# STM32F407VE.net
KiCad netlist of a schematic drawn in Altium Designer
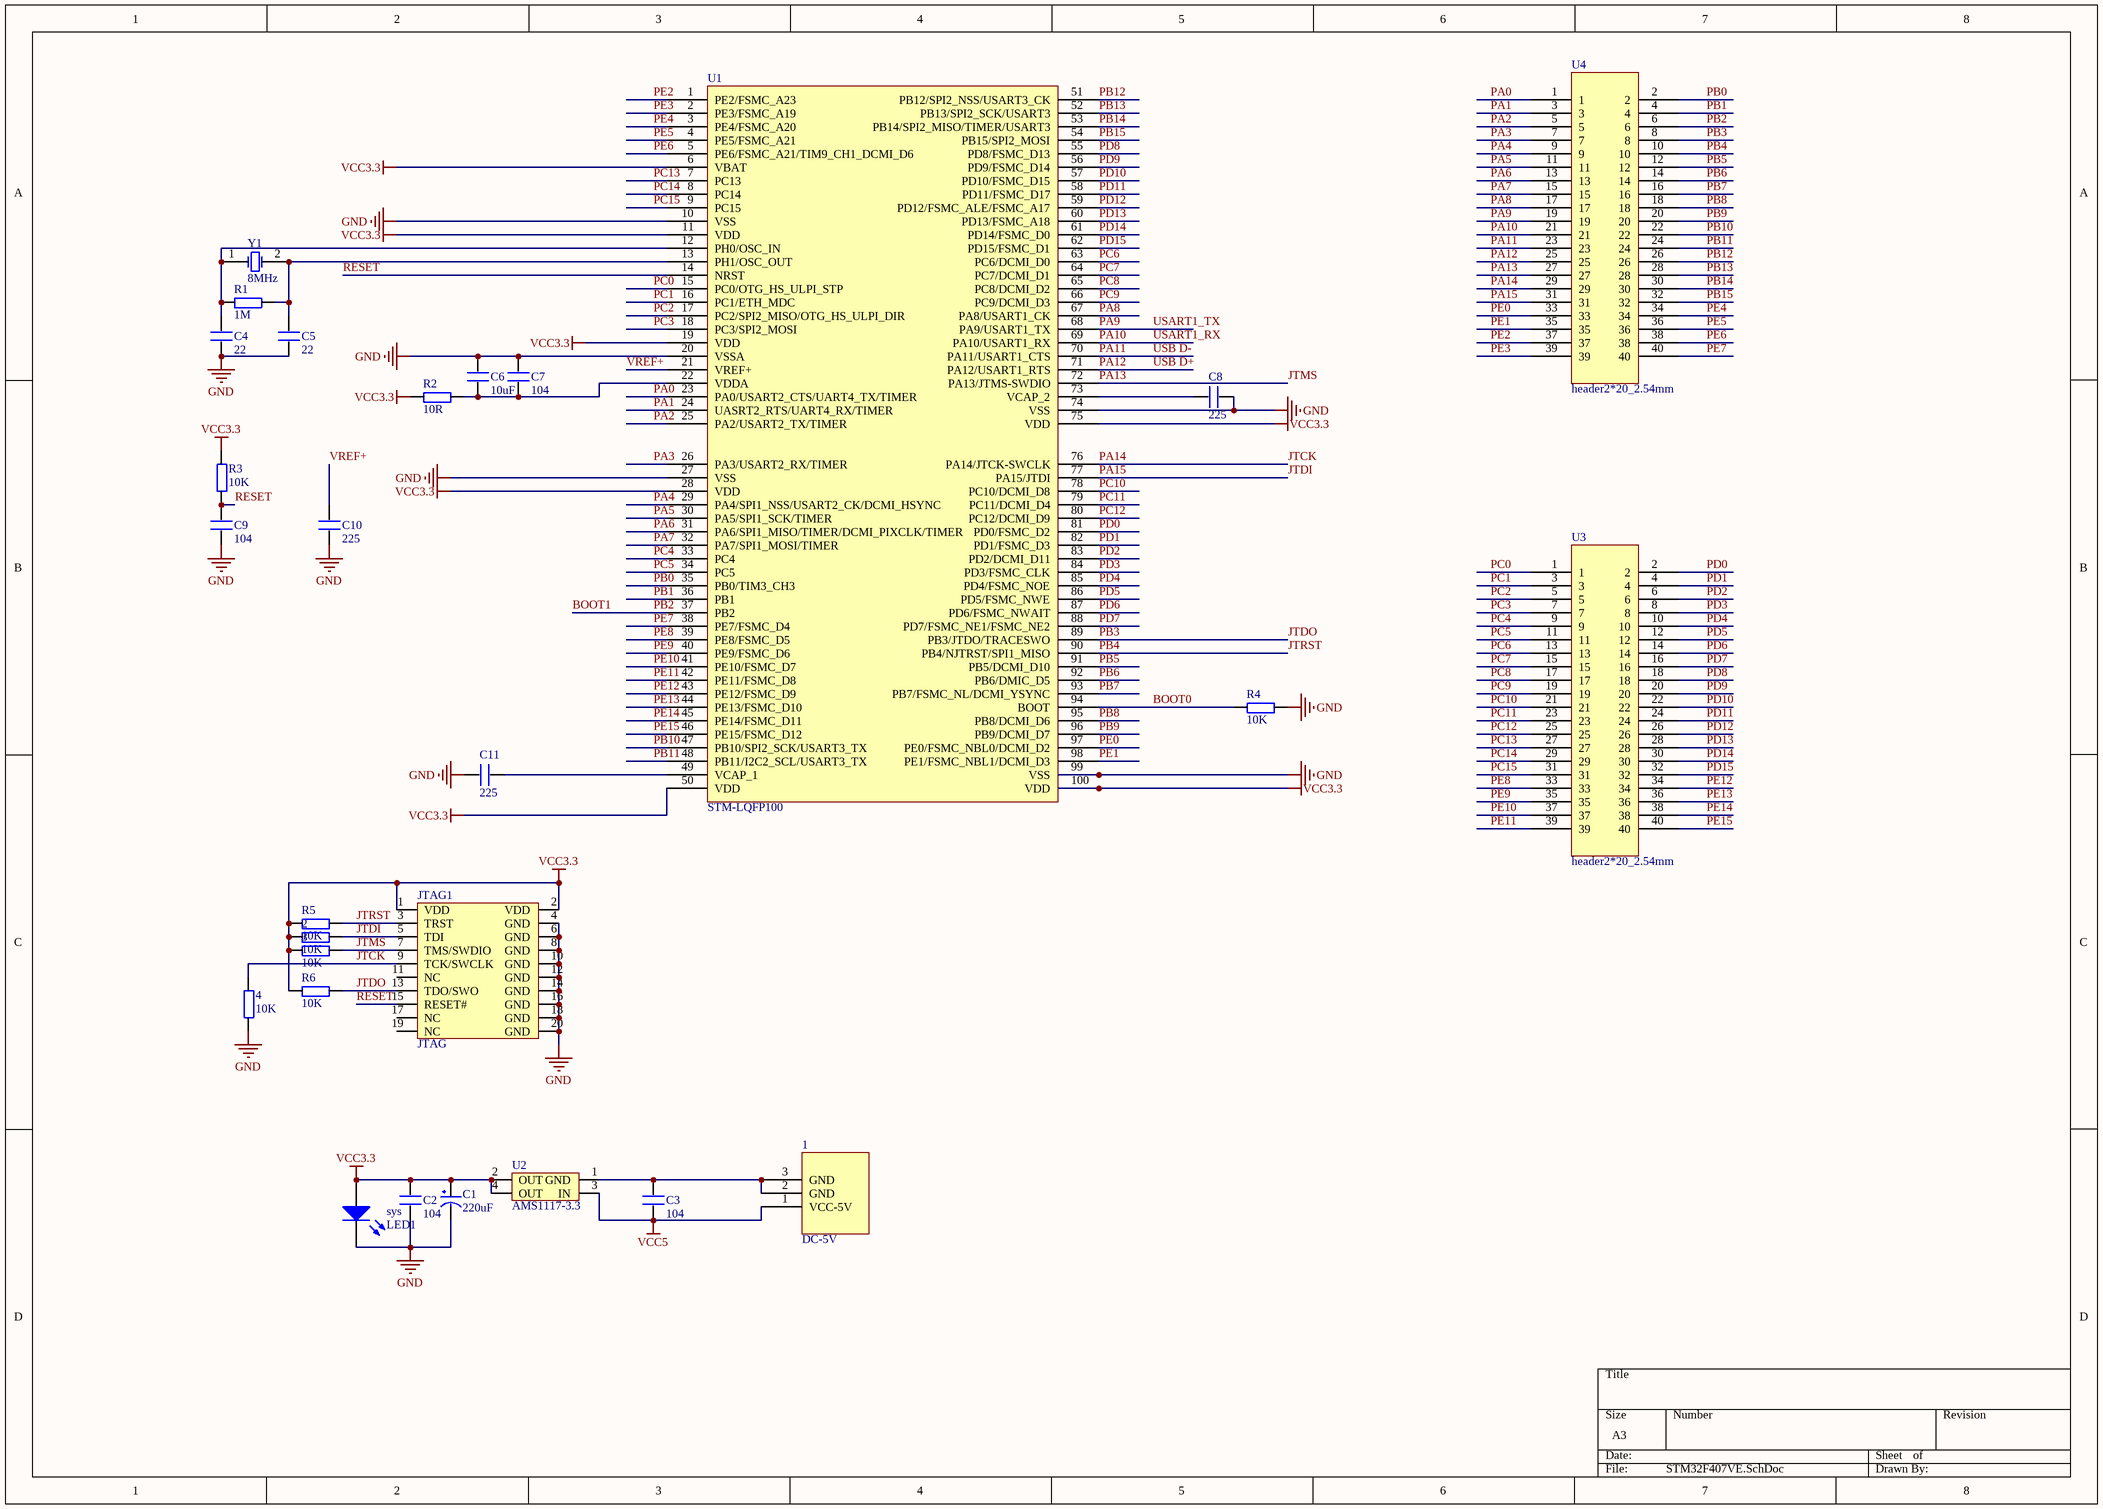
[diagram p0: STM32F407VE.SchDoc]

(export (version "E")
  (design (tool "Eeschema 10.0.6"))
  (components
    (comp (ref "1") (value "DC-5V") (footprint "DC-5V") (libsource (lib "Schlib1") (part "DC-5V")))
    (comp (ref "2") (value "10K") (footprint "0603P") (libsource (lib "Explorer STM32F407封装库") (part "R")))
    (comp (ref "3") (value "10K") (footprint "0603P") (libsource (lib "Explorer STM32F407封装库") (part "R")))
    (comp (ref "4") (value "10K") (footprint "0603P") (libsource (lib "Explorer STM32F407封装库") (part "R")))
    (comp (ref "C1")
      (value "220uF")
      (footprint "CC6.56.5")
      (libsource (lib "Explorer STM32F407封装库") (part "CAP"))
    )
    (comp (ref "C2") (value "104") (footprint "0603P") (libsource (lib "Explorer STM32F407封装库") (part "C")))
    (comp (ref "C3") (value "104") (footprint "0603P") (libsource (lib "Explorer STM32F407封装库") (part "C")))
    (comp (ref "C4") (value "22") (footprint "0603P") (libsource (lib "Explorer STM32F407封装库") (part "C")))
    (comp (ref "C5") (value "22") (footprint "0603P") (libsource (lib "Explorer STM32F407封装库") (part "C")))
    (comp (ref "C6") (value "10uF") (footprint "0603P") (libsource (lib "Explorer STM32F407封装库") (part "C")))
    (comp (ref "C7") (value "104") (footprint "0603P") (libsource (lib "Explorer STM32F407封装库") (part "C")))
    (comp (ref "C8") (value "225") (footprint "0603P") (libsource (lib "Explorer STM32F407封装库") (part "C")))
    (comp (ref "C9") (value "104") (footprint "0603P") (libsource (lib "Explorer STM32F407封装库") (part "C")))
    (comp (ref "C10") (value "225") (footprint "0603P") (libsource (lib "Explorer STM32F407封装库") (part "C")))
    (comp (ref "C11") (value "225") (footprint "0603P") (libsource (lib "Explorer STM32F407封装库") (part "C")))
    (comp (ref "JTAG1")
      (value "JTAG")
      (footprint "JTAG_20")
      (libsource (lib "Explorer STM32F407封装库") (part "JTAG"))
    )
    (comp (ref "R1") (value "1M") (footprint "0603P") (libsource (lib "Explorer STM32F407封装库") (part "R")))
    (comp (ref "R2") (value "10R") (footprint "0603P") (libsource (lib "Explorer STM32F407封装库") (part "R")))
    (comp (ref "R3") (value "10K") (footprint "0603P") (libsource (lib "Explorer STM32F407封装库") (part "R")))
    (comp (ref "R4") (value "10K") (footprint "0603P") (libsource (lib "Explorer STM32F407封装库") (part "R")))
    (comp (ref "R5") (value "10K") (footprint "0603P") (libsource (lib "Explorer STM32F407封装库") (part "R")))
    (comp (ref "R6") (value "10K") (footprint "0603P") (libsource (lib "Explorer STM32F407封装库") (part "R")))
    (comp (ref "sys")
      (value "LED1")
      (footprint "SMDLED")
      (description "Typical RED, GREEN, YELLOW, AMBER GaAs LED")
      (fields (field (name "PUBLISHER") "Altium Limited"))
      (libsource (lib "Explorer STM32F407封装库") (part "LED2"))
    )
    (comp (ref "U1")
      (value "STM-LQFP100")
      (footprint "STM-LQFP100_N")
      (libsource (lib "Schlib1") (part "STM-LQFP100"))
    )
    (comp (ref "U2")
      (value "AMS1117-3.3")
      (footprint "AMS1117")
      (libsource (lib "Explorer STM32F407封装库") (part "AMS1117"))
    )
    (comp (ref "U3")
      (value "header2*20_2.54mm")
      (footprint "header2*20_2.54mm")
      (libsource (lib "Schlib1") (part "header2*20_2.54mm"))
    )
    (comp (ref "U4")
      (value "header2*20_2.54mm")
      (footprint "header2*20_2.54mm")
      (libsource (lib "Schlib1") (part "header2*20_2.54mm"))
    )
    (comp (ref "Y1")
      (value "8MHz")
      (footprint "XTAL_US")
      (description "Crystal Oscillator")
      (fields (field (name "PUBLISHER") "Altium Limited"))
      (libsource (lib "Explorer STM32F407封装库") (part "XTAL"))
    )
  )
  (nets
    (net (code "1") (name "/BOOT0") (class "Default")
      (node (ref "R4") (pin "1") (pintype "passive"))
      (node (ref "U1") (pin "94") (pinfunction "BOOT_94") (pintype "passive"))
    )
    (net (code "2") (name "/BOOT1") (class "Default")
      (node (ref "U1") (pin "37") (pinfunction "PB2_37") (pintype "passive"))
      (node (ref "U4") (pin "6") (pinfunction "6_6") (pintype "passive"))
    )
    (net (code "3") (name "/JTCK") (class "Default")
      (node (ref "4") (pin "2") (pintype "passive"))
      (node (ref "JTAG1") (pin "9") (pinfunction "TCK/SWCLK_9") (pintype "passive"))
      (node (ref "U1") (pin "76") (pinfunction "PA14/JTCK-SWCLK_76") (pintype "passive"))
      (node (ref "U4") (pin "29") (pinfunction "29_29") (pintype "passive"))
    )
    (net (code "4") (name "/JTDI") (class "Default")
      (node (ref "2") (pin "2") (pintype "passive"))
      (node (ref "JTAG1") (pin "5") (pinfunction "TDI_5") (pintype "passive"))
      (node (ref "U1") (pin "77") (pinfunction "PA15/JTDI_77") (pintype "passive"))
      (node (ref "U4") (pin "31") (pinfunction "31_31") (pintype "passive"))
    )
    (net (code "5") (name "/JTDO") (class "Default")
      (node (ref "JTAG1") (pin "13") (pinfunction "TDO/SWO_13") (pintype "passive"))
      (node (ref "R6") (pin "2") (pintype "passive"))
      (node (ref "U1") (pin "89") (pinfunction "PB3/JTDO/TRACESWO_89") (pintype "passive"))
      (node (ref "U4") (pin "8") (pinfunction "8_8") (pintype "passive"))
    )
    (net (code "6") (name "/JTMS") (class "Default")
      (node (ref "3") (pin "2") (pintype "passive"))
      (node (ref "JTAG1") (pin "7") (pinfunction "TMS/SWDIO_7") (pintype "passive"))
      (node (ref "U1") (pin "72") (pinfunction "PA13/JTMS-SWDIO_72") (pintype "passive"))
      (node (ref "U4") (pin "27") (pinfunction "27_27") (pintype "passive"))
    )
    (net (code "7") (name "/JTRST") (class "Default")
      (node (ref "JTAG1") (pin "3") (pinfunction "TRST_3") (pintype "passive"))
      (node (ref "R5") (pin "2") (pintype "passive"))
      (node (ref "U1") (pin "90") (pinfunction "PB4/NJTRST/SPI1_MISO_90") (pintype "passive"))
      (node (ref "U4") (pin "10") (pinfunction "10_10") (pintype "passive"))
    )
    (net (code "8") (name "/PA0") (class "Default")
      (node (ref "U1") (pin "23") (pinfunction "PA0/USART2_CTS/UART4_TX/TIMER_23") (pintype "passive"))
      (node (ref "U4") (pin "1") (pinfunction "1_1") (pintype "passive"))
    )
    (net (code "9") (name "/PA1") (class "Default")
      (node (ref "U1") (pin "24") (pinfunction "UASRT2_RTS/UART4_RX/TIMER_24") (pintype "passive"))
      (node (ref "U4") (pin "3") (pinfunction "3_3") (pintype "passive"))
    )
    (net (code "10") (name "/PA2") (class "Default")
      (node (ref "U1") (pin "25") (pinfunction "PA2/USART2_TX/TIMER_25") (pintype "passive"))
      (node (ref "U4") (pin "5") (pinfunction "5_5") (pintype "passive"))
    )
    (net (code "11") (name "/PA3") (class "Default")
      (node (ref "U1") (pin "26") (pinfunction "PA3/USART2_RX/TIMER_26") (pintype "passive"))
      (node (ref "U4") (pin "7") (pinfunction "7_7") (pintype "passive"))
    )
    (net (code "12") (name "/PA4") (class "Default")
      (node (ref "U1") (pin "29") (pinfunction "PA4/SPI1_NSS/USART2_CK/DCMI_HSYNC_29") (pintype "passive"))
      (node (ref "U4") (pin "9") (pinfunction "9_9") (pintype "passive"))
    )
    (net (code "13") (name "/PA5") (class "Default")
      (node (ref "U1") (pin "30") (pinfunction "PA5/SPI1_SCK/TIMER_30") (pintype "passive"))
      (node (ref "U4") (pin "11") (pinfunction "11_11") (pintype "passive"))
    )
    (net (code "14") (name "/PA6") (class "Default")
      (node (ref "U1") (pin "31") (pinfunction "PA6/SPI1_MISO/TIMER/DCMI_PIXCLK/TIMER_31") (pintype "passive"))
      (node (ref "U4") (pin "13") (pinfunction "13_13") (pintype "passive"))
    )
    (net (code "15") (name "/PA7") (class "Default")
      (node (ref "U1") (pin "32") (pinfunction "PA7/SPI1_MOSI/TIMER_32") (pintype "passive"))
      (node (ref "U4") (pin "15") (pinfunction "15_15") (pintype "passive"))
    )
    (net (code "16") (name "/PA8") (class "Default")
      (node (ref "U1") (pin "67") (pinfunction "PA8/USART1_CK_67") (pintype "passive"))
      (node (ref "U4") (pin "17") (pinfunction "17_17") (pintype "passive"))
    )
    (net (code "17") (name "/PA9") (class "Default")
      (node (ref "U1") (pin "68") (pinfunction "PA9/USART1_TX_68") (pintype "passive"))
      (node (ref "U4") (pin "19") (pinfunction "19_19") (pintype "passive"))
    )
    (net (code "18") (name "/PA10") (class "Default")
      (node (ref "U1") (pin "69") (pinfunction "PA10/USART1_RX_69") (pintype "passive"))
      (node (ref "U4") (pin "21") (pinfunction "21_21") (pintype "passive"))
    )
    (net (code "19") (name "/PA11") (class "Default")
      (node (ref "U1") (pin "70") (pinfunction "PA11/USART1_CTS_70") (pintype "passive"))
      (node (ref "U4") (pin "23") (pinfunction "23_23") (pintype "passive"))
    )
    (net (code "20") (name "/PA12") (class "Default")
      (node (ref "U1") (pin "71") (pinfunction "PA12/USART1_RTS_71") (pintype "passive"))
      (node (ref "U4") (pin "25") (pinfunction "25_25") (pintype "passive"))
    )
    (net (code "21") (name "/PB0") (class "Default")
      (node (ref "U1") (pin "35") (pinfunction "PB0/TIM3_CH3_35") (pintype "passive"))
      (node (ref "U4") (pin "2") (pinfunction "2_2") (pintype "passive"))
    )
    (net (code "22") (name "/PB1") (class "Default")
      (node (ref "U1") (pin "36") (pinfunction "PB1_36") (pintype "passive"))
      (node (ref "U4") (pin "4") (pinfunction "4_4") (pintype "passive"))
    )
    (net (code "23") (name "/PB5") (class "Default")
      (node (ref "U1") (pin "91") (pinfunction "PB5/DCMI_D10_91") (pintype "passive"))
      (node (ref "U4") (pin "12") (pinfunction "12_12") (pintype "passive"))
    )
    (net (code "24") (name "/PB6") (class "Default")
      (node (ref "U1") (pin "92") (pinfunction "PB6/DMIC_D5_92") (pintype "passive"))
      (node (ref "U4") (pin "14") (pinfunction "14_14") (pintype "passive"))
    )
    (net (code "25") (name "/PB7") (class "Default")
      (node (ref "U1") (pin "93") (pinfunction "PB7/FSMC_NL/DCMI_YSYNC_93") (pintype "passive"))
      (node (ref "U4") (pin "16") (pinfunction "16_16") (pintype "passive"))
    )
    (net (code "26") (name "/PB8") (class "Default")
      (node (ref "U1") (pin "95") (pinfunction "PB8/DCMI_D6_95") (pintype "passive"))
      (node (ref "U4") (pin "18") (pinfunction "18_18") (pintype "passive"))
    )
    (net (code "27") (name "/PB9") (class "Default")
      (node (ref "U1") (pin "96") (pinfunction "PB9/DCMI_D7_96") (pintype "passive"))
      (node (ref "U4") (pin "20") (pinfunction "20_20") (pintype "passive"))
    )
    (net (code "28") (name "/PB10") (class "Default")
      (node (ref "U1") (pin "47") (pinfunction "PB10/SPI2_SCK/USART3_TX_47") (pintype "passive"))
      (node (ref "U4") (pin "22") (pinfunction "22_22") (pintype "passive"))
    )
    (net (code "29") (name "/PB11") (class "Default")
      (node (ref "U1") (pin "48") (pinfunction "PB11/I2C2_SCL/USART3_TX_48") (pintype "passive"))
      (node (ref "U4") (pin "24") (pinfunction "24_24") (pintype "passive"))
    )
    (net (code "30") (name "/PB12") (class "Default")
      (node (ref "U1") (pin "51") (pinfunction "PB12/SPI2_NSS/USART3_CK_51") (pintype "passive"))
      (node (ref "U4") (pin "26") (pinfunction "26_26") (pintype "passive"))
    )
    (net (code "31") (name "/PB13") (class "Default")
      (node (ref "U1") (pin "52") (pinfunction "PB13/SPI2_SCK/USART3_52") (pintype "passive"))
      (node (ref "U4") (pin "28") (pinfunction "28_28") (pintype "passive"))
    )
    (net (code "32") (name "/PB14") (class "Default")
      (node (ref "U1") (pin "53") (pinfunction "PB14/SPI2_MISO/TIMER/USART3_53") (pintype "passive"))
      (node (ref "U4") (pin "30") (pinfunction "30_30") (pintype "passive"))
    )
    (net (code "33") (name "/PB15") (class "Default")
      (node (ref "U1") (pin "54") (pinfunction "PB15/SPI2_MOSI_54") (pintype "passive"))
      (node (ref "U4") (pin "32") (pinfunction "32_32") (pintype "passive"))
    )
    (net (code "34") (name "/PC0") (class "Default")
      (node (ref "U1") (pin "15") (pinfunction "PC0/OTG_HS_ULPI_STP_15") (pintype "passive"))
      (node (ref "U3") (pin "1") (pinfunction "1_1") (pintype "passive"))
    )
    (net (code "35") (name "/PC1") (class "Default")
      (node (ref "U1") (pin "16") (pinfunction "PC1/ETH_MDC_16") (pintype "passive"))
      (node (ref "U3") (pin "3") (pinfunction "3_3") (pintype "passive"))
    )
    (net (code "36") (name "/PC2") (class "Default")
      (node (ref "U1") (pin "17") (pinfunction "PC2/SPI2_MISO/OTG_HS_ULPI_DIR_17") (pintype "passive"))
      (node (ref "U3") (pin "5") (pinfunction "5_5") (pintype "passive"))
    )
    (net (code "37") (name "/PC3") (class "Default")
      (node (ref "U1") (pin "18") (pinfunction "PC3/SPI2_MOSI_18") (pintype "passive"))
      (node (ref "U3") (pin "7") (pinfunction "7_7") (pintype "passive"))
    )
    (net (code "38") (name "/PC4") (class "Default")
      (node (ref "U1") (pin "33") (pinfunction "PC4_33") (pintype "passive"))
      (node (ref "U3") (pin "9") (pinfunction "9_9") (pintype "passive"))
    )
    (net (code "39") (name "/PC5") (class "Default")
      (node (ref "U1") (pin "34") (pinfunction "PC5_34") (pintype "passive"))
      (node (ref "U3") (pin "11") (pinfunction "11_11") (pintype "passive"))
    )
    (net (code "40") (name "/PC6") (class "Default")
      (node (ref "U1") (pin "63") (pinfunction "PC6/DCMI_D0_63") (pintype "passive"))
      (node (ref "U3") (pin "13") (pinfunction "13_13") (pintype "passive"))
    )
    (net (code "41") (name "/PC7") (class "Default")
      (node (ref "U1") (pin "64") (pinfunction "PC7/DCMI_D1_64") (pintype "passive"))
      (node (ref "U3") (pin "15") (pinfunction "15_15") (pintype "passive"))
    )
    (net (code "42") (name "/PC8") (class "Default")
      (node (ref "U1") (pin "65") (pinfunction "PC8/DCMI_D2_65") (pintype "passive"))
      (node (ref "U3") (pin "17") (pinfunction "17_17") (pintype "passive"))
    )
    (net (code "43") (name "/PC9") (class "Default")
      (node (ref "U1") (pin "66") (pinfunction "PC9/DCMI_D3_66") (pintype "passive"))
      (node (ref "U3") (pin "19") (pinfunction "19_19") (pintype "passive"))
    )
    (net (code "44") (name "/PC10") (class "Default")
      (node (ref "U1") (pin "78") (pinfunction "PC10/DCMI_D8_78") (pintype "passive"))
      (node (ref "U3") (pin "21") (pinfunction "21_21") (pintype "passive"))
    )
    (net (code "45") (name "/PC11") (class "Default")
      (node (ref "U1") (pin "79") (pinfunction "PC11/DCMI_D4_79") (pintype "passive"))
      (node (ref "U3") (pin "23") (pinfunction "23_23") (pintype "passive"))
    )
    (net (code "46") (name "/PC12") (class "Default")
      (node (ref "U1") (pin "80") (pinfunction "PC12/DCMI_D9_80") (pintype "passive"))
      (node (ref "U3") (pin "25") (pinfunction "25_25") (pintype "passive"))
    )
    (net (code "47") (name "/PC13") (class "Default")
      (node (ref "U1") (pin "7") (pinfunction "PC13_7") (pintype "passive"))
      (node (ref "U3") (pin "27") (pinfunction "27_27") (pintype "passive"))
    )
    (net (code "48") (name "/PC14") (class "Default")
      (node (ref "U1") (pin "8") (pinfunction "PC14_8") (pintype "passive"))
      (node (ref "U3") (pin "29") (pinfunction "29_29") (pintype "passive"))
    )
    (net (code "49") (name "/PC15") (class "Default")
      (node (ref "U1") (pin "9") (pinfunction "PC15_9") (pintype "passive"))
      (node (ref "U3") (pin "31") (pinfunction "31_31") (pintype "passive"))
    )
    (net (code "50") (name "/PD0") (class "Default")
      (node (ref "U1") (pin "81") (pinfunction "PD0/FSMC_D2_81") (pintype "passive"))
      (node (ref "U3") (pin "2") (pinfunction "2_2") (pintype "passive"))
    )
    (net (code "51") (name "/PD1") (class "Default")
      (node (ref "U1") (pin "82") (pinfunction "PD1/FSMC_D3_82") (pintype "passive"))
      (node (ref "U3") (pin "4") (pinfunction "4_4") (pintype "passive"))
    )
    (net (code "52") (name "/PD2") (class "Default")
      (node (ref "U1") (pin "83") (pinfunction "PD2/DCMI_D11_83") (pintype "passive"))
      (node (ref "U3") (pin "6") (pinfunction "6_6") (pintype "passive"))
    )
    (net (code "53") (name "/PD3") (class "Default")
      (node (ref "U1") (pin "84") (pinfunction "PD3/FSMC_CLK_84") (pintype "passive"))
      (node (ref "U3") (pin "8") (pinfunction "8_8") (pintype "passive"))
    )
    (net (code "54") (name "/PD4") (class "Default")
      (node (ref "U1") (pin "85") (pinfunction "PD4/FSMC_NOE_85") (pintype "passive"))
      (node (ref "U3") (pin "10") (pinfunction "10_10") (pintype "passive"))
    )
    (net (code "55") (name "/PD5") (class "Default")
      (node (ref "U1") (pin "86") (pinfunction "PD5/FSMC_NWE_86") (pintype "passive"))
      (node (ref "U3") (pin "12") (pinfunction "12_12") (pintype "passive"))
    )
    (net (code "56") (name "/PD6") (class "Default")
      (node (ref "U1") (pin "87") (pinfunction "PD6/FSMC_NWAIT_87") (pintype "passive"))
      (node (ref "U3") (pin "14") (pinfunction "14_14") (pintype "passive"))
    )
    (net (code "57") (name "/PD7") (class "Default")
      (node (ref "U1") (pin "88") (pinfunction "PD7/FSMC_NE1/FSMC_NE2_88") (pintype "passive"))
      (node (ref "U3") (pin "16") (pinfunction "16_16") (pintype "passive"))
    )
    (net (code "58") (name "/PD8") (class "Default")
      (node (ref "U1") (pin "55") (pinfunction "PD8/FSMC_D13_55") (pintype "passive"))
      (node (ref "U3") (pin "18") (pinfunction "18_18") (pintype "passive"))
    )
    (net (code "59") (name "/PD9") (class "Default")
      (node (ref "U1") (pin "56") (pinfunction "PD9/FSMC_D14_56") (pintype "passive"))
      (node (ref "U3") (pin "20") (pinfunction "20_20") (pintype "passive"))
    )
    (net (code "60") (name "/PD10") (class "Default")
      (node (ref "U1") (pin "57") (pinfunction "PD10/FSMC_D15_57") (pintype "passive"))
      (node (ref "U3") (pin "22") (pinfunction "22_22") (pintype "passive"))
    )
    (net (code "61") (name "/PD11") (class "Default")
      (node (ref "U1") (pin "58") (pinfunction "PD11/FSMC_D17_58") (pintype "passive"))
      (node (ref "U3") (pin "24") (pinfunction "24_24") (pintype "passive"))
    )
    (net (code "62") (name "/PD12") (class "Default")
      (node (ref "U1") (pin "59") (pinfunction "PD12/FSMC_ALE/FSMC_A17_59") (pintype "passive"))
      (node (ref "U3") (pin "26") (pinfunction "26_26") (pintype "passive"))
    )
    (net (code "63") (name "/PD13") (class "Default")
      (node (ref "U1") (pin "60") (pinfunction "PD13/FSMC_A18_60") (pintype "passive"))
      (node (ref "U3") (pin "28") (pinfunction "28_28") (pintype "passive"))
    )
    (net (code "64") (name "/PD14") (class "Default")
      (node (ref "U1") (pin "61") (pinfunction "PD14/FSMC_D0_61") (pintype "passive"))
      (node (ref "U3") (pin "30") (pinfunction "30_30") (pintype "passive"))
    )
    (net (code "65") (name "/PD15") (class "Default")
      (node (ref "U1") (pin "62") (pinfunction "PD15/FSMC_D1_62") (pintype "passive"))
      (node (ref "U3") (pin "32") (pinfunction "32_32") (pintype "passive"))
    )
    (net (code "66") (name "/PE0") (class "Default")
      (node (ref "U1") (pin "97") (pinfunction "PE0/FSMC_NBL0/DCMI_D2_97") (pintype "passive"))
      (node (ref "U4") (pin "33") (pinfunction "33_33") (pintype "passive"))
    )
    (net (code "67") (name "/PE1") (class "Default")
      (node (ref "U1") (pin "98") (pinfunction "PE1/FSMC_NBL1/DCMI_D3_98") (pintype "passive"))
      (node (ref "U4") (pin "35") (pinfunction "35_35") (pintype "passive"))
    )
    (net (code "68") (name "/PE2") (class "Default")
      (node (ref "U1") (pin "1") (pinfunction "PE2/FSMC_A23_1") (pintype "passive"))
      (node (ref "U4") (pin "37") (pinfunction "37_37") (pintype "passive"))
    )
    (net (code "69") (name "/PE3") (class "Default")
      (node (ref "U1") (pin "2") (pinfunction "PE3/FSMC_A19_2") (pintype "passive"))
      (node (ref "U4") (pin "39") (pinfunction "39_39") (pintype "passive"))
    )
    (net (code "70") (name "/PE4") (class "Default")
      (node (ref "U1") (pin "3") (pinfunction "PE4/FSMC_A20_3") (pintype "passive"))
      (node (ref "U4") (pin "34") (pinfunction "34_34") (pintype "passive"))
    )
    (net (code "71") (name "/PE5") (class "Default")
      (node (ref "U1") (pin "4") (pinfunction "PE5/FSMC_A21_4") (pintype "passive"))
      (node (ref "U4") (pin "36") (pinfunction "36_36") (pintype "passive"))
    )
    (net (code "72") (name "/PE6") (class "Default")
      (node (ref "U1") (pin "5") (pinfunction "PE6/FSMC_A21/TIM9_CH1_DCMI_D6_5") (pintype "passive"))
      (node (ref "U4") (pin "38") (pinfunction "38_38") (pintype "passive"))
    )
    (net (code "73") (name "/PE7") (class "Default")
      (node (ref "U1") (pin "38") (pinfunction "PE7/FSMC_D4_38") (pintype "passive"))
      (node (ref "U4") (pin "40") (pinfunction "40_40") (pintype "passive"))
    )
    (net (code "74") (name "/PE8") (class "Default")
      (node (ref "U1") (pin "39") (pinfunction "PE8/FSMC_D5_39") (pintype "passive"))
      (node (ref "U3") (pin "33") (pinfunction "33_33") (pintype "passive"))
    )
    (net (code "75") (name "/PE9") (class "Default")
      (node (ref "U1") (pin "40") (pinfunction "PE9/FSMC_D6_40") (pintype "passive"))
      (node (ref "U3") (pin "35") (pinfunction "35_35") (pintype "passive"))
    )
    (net (code "76") (name "/PE10") (class "Default")
      (node (ref "U1") (pin "41") (pinfunction "PE10/FSMC_D7_41") (pintype "passive"))
      (node (ref "U3") (pin "37") (pinfunction "37_37") (pintype "passive"))
    )
    (net (code "77") (name "/PE11") (class "Default")
      (node (ref "U1") (pin "42") (pinfunction "PE11/FSMC_D8_42") (pintype "passive"))
      (node (ref "U3") (pin "39") (pinfunction "39_39") (pintype "passive"))
    )
    (net (code "78") (name "/PE12") (class "Default")
      (node (ref "U1") (pin "43") (pinfunction "PE12/FSMC_D9_43") (pintype "passive"))
      (node (ref "U3") (pin "34") (pinfunction "34_34") (pintype "passive"))
    )
    (net (code "79") (name "/PE13") (class "Default")
      (node (ref "U1") (pin "44") (pinfunction "PE13/FSMC_D10_44") (pintype "passive"))
      (node (ref "U3") (pin "36") (pinfunction "36_36") (pintype "passive"))
    )
    (net (code "80") (name "/PE14") (class "Default")
      (node (ref "U1") (pin "45") (pinfunction "PE14/FSMC_D11_45") (pintype "passive"))
      (node (ref "U3") (pin "38") (pinfunction "38_38") (pintype "passive"))
    )
    (net (code "81") (name "/PE15") (class "Default")
      (node (ref "U1") (pin "46") (pinfunction "PE15/FSMC_D12_46") (pintype "passive"))
      (node (ref "U3") (pin "40") (pinfunction "40_40") (pintype "passive"))
    )
    (net (code "82") (name "/RESET") (class "Default")
      (node (ref "C9") (pin "2") (pintype "passive"))
      (node (ref "JTAG1") (pin "15") (pinfunction "RESET#_15") (pintype "passive"))
      (node (ref "R3") (pin "1") (pintype "passive"))
      (node (ref "U1") (pin "14") (pinfunction "NRST_14") (pintype "passive"))
    )
    (net (code "83") (name "/VREF+") (class "Default")
      (node (ref "C10") (pin "2") (pintype "passive"))
      (node (ref "U1") (pin "21") (pinfunction "VREF+_21") (pintype "passive"))
    )
    (net (code "84") (name "GND") (class "Default")
      (node (ref "4") (pin "1") (pintype "passive"))
      (node (ref "C1") (pin "2") (pinfunction "GND_2") (pintype "passive"))
      (node (ref "C10") (pin "1") (pintype "passive"))
      (node (ref "C11") (pin "1") (pintype "passive"))
      (node (ref "C2") (pin "1") (pintype "passive"))
      (node (ref "C4") (pin "1") (pintype "passive"))
      (node (ref "C5") (pin "1") (pintype "passive"))
      (node (ref "C6") (pin "2") (pintype "passive"))
      (node (ref "C7") (pin "2") (pintype "passive"))
      (node (ref "C8") (pin "2") (pintype "passive"))
      (node (ref "C9") (pin "1") (pintype "passive"))
      (node (ref "JTAG1") (pin "10") (pinfunction "GND_10") (pintype "passive"))
      (node (ref "JTAG1") (pin "12") (pinfunction "GND_12") (pintype "passive"))
      (node (ref "JTAG1") (pin "14") (pinfunction "GND_14") (pintype "passive"))
      (node (ref "JTAG1") (pin "16") (pinfunction "GND_16") (pintype "passive"))
      (node (ref "JTAG1") (pin "18") (pinfunction "GND_18") (pintype "passive"))
      (node (ref "JTAG1") (pin "20") (pinfunction "GND_20") (pintype "passive"))
      (node (ref "JTAG1") (pin "4") (pinfunction "GND_4") (pintype "passive"))
      (node (ref "JTAG1") (pin "6") (pinfunction "GND_6") (pintype "passive"))
      (node (ref "JTAG1") (pin "8") (pinfunction "GND_8") (pintype "passive"))
      (node (ref "R4") (pin "2") (pintype "passive"))
      (node (ref "U1") (pin "10") (pinfunction "VSS_10") (pintype "passive"))
      (node (ref "U1") (pin "20") (pinfunction "VSSA_20") (pintype "passive"))
      (node (ref "U1") (pin "27") (pinfunction "VSS_27") (pintype "passive"))
      (node (ref "U1") (pin "74") (pinfunction "VSS_74") (pintype "passive"))
      (node (ref "U1") (pin "99") (pinfunction "VSS_99") (pintype "passive"))
      (node (ref "sys") (pin "2") (pinfunction "K_2") (pintype "passive"))
    )
    (net (code "85") (name "Net-(U1-PH0{slash}OSC_IN)") (class "Default")
      (node (ref "C4") (pin "2") (pintype "passive"))
      (node (ref "R1") (pin "1") (pintype "passive"))
      (node (ref "U1") (pin "12") (pinfunction "PH0/OSC_IN_12") (pintype "passive"))
      (node (ref "Y1") (pin "1") (pinfunction "OSC1_1") (pintype "passive"))
    )
    (net (code "86") (name "Net-(U1-PH1{slash}OSC_OUT)") (class "Default")
      (node (ref "C5") (pin "2") (pintype "passive"))
      (node (ref "R1") (pin "2") (pintype "passive"))
      (node (ref "U1") (pin "13") (pinfunction "PH1/OSC_OUT_13") (pintype "passive"))
      (node (ref "Y1") (pin "2") (pinfunction "OSC2_2") (pintype "passive"))
    )
    (net (code "87") (name "Net-(U1-VCAP_1)") (class "Default")
      (node (ref "C11") (pin "2") (pintype "passive"))
      (node (ref "U1") (pin "49") (pinfunction "VCAP_1_49") (pintype "passive"))
    )
    (net (code "88") (name "Net-(U1-VCAP_2)") (class "Default")
      (node (ref "C8") (pin "1") (pintype "passive"))
      (node (ref "U1") (pin "73") (pinfunction "VCAP_2_73") (pintype "passive"))
    )
    (net (code "89") (name "Net-(U1-VDDA)") (class "Default")
      (node (ref "C6") (pin "1") (pintype "passive"))
      (node (ref "C7") (pin "1") (pintype "passive"))
      (node (ref "R2") (pin "2") (pintype "passive"))
      (node (ref "U1") (pin "22") (pinfunction "VDDA_22") (pintype "passive"))
    )
    (net (code "90") (name "Net-(U2-GND)") (class "Default")
      (node (ref "1") (pin "2") (pinfunction "GND_2") (pintype "passive"))
      (node (ref "1") (pin "3") (pinfunction "GND_3") (pintype "passive"))
      (node (ref "C3") (pin "2") (pintype "passive"))
      (node (ref "U2") (pin "1") (pinfunction "GND_1") (pintype "passive"))
    )
    (net (code "91") (name "VCC3.3") (class "Default")
      (node (ref "2") (pin "1") (pintype "passive"))
      (node (ref "3") (pin "1") (pintype "passive"))
      (node (ref "C1") (pin "1") (pinfunction "VCC_1") (pintype "passive"))
      (node (ref "C2") (pin "2") (pintype "passive"))
      (node (ref "JTAG1") (pin "1") (pinfunction "VDD_1") (pintype "passive"))
      (node (ref "JTAG1") (pin "2") (pinfunction "VDD_2") (pintype "passive"))
      (node (ref "R2") (pin "1") (pintype "passive"))
      (node (ref "R3") (pin "2") (pintype "passive"))
      (node (ref "R5") (pin "1") (pintype "passive"))
      (node (ref "R6") (pin "1") (pintype "passive"))
      (node (ref "U1") (pin "100") (pinfunction "VDD_100") (pintype "passive"))
      (node (ref "U1") (pin "11") (pinfunction "VDD_11") (pintype "passive"))
      (node (ref "U1") (pin "19") (pinfunction "VDD_19") (pintype "passive"))
      (node (ref "U1") (pin "28") (pinfunction "VDD_28") (pintype "passive"))
      (node (ref "U1") (pin "50") (pinfunction "VDD_50") (pintype "passive"))
      (node (ref "U1") (pin "6") (pinfunction "VBAT_6") (pintype "passive"))
      (node (ref "U1") (pin "75") (pinfunction "VDD_75") (pintype "passive"))
      (node (ref "U2") (pin "2") (pinfunction "OUT_2") (pintype "passive"))
      (node (ref "U2") (pin "4") (pinfunction "OUT_4") (pintype "passive"))
      (node (ref "sys") (pin "1") (pinfunction "A_1") (pintype "passive"))
    )
    (net (code "92") (name "VCC5") (class "Default")
      (node (ref "1") (pin "1") (pinfunction "VCC-5V_1") (pintype "passive"))
      (node (ref "C3") (pin "1") (pintype "passive"))
      (node (ref "U2") (pin "3") (pinfunction "IN_3") (pintype "passive"))
    )
    (net (code "93") (name "unconnected-(JTAG1-NC-Pad11)") (class "Default")
      (node (ref "JTAG1") (pin "11") (pinfunction "NC_11") (pintype "passive"))
    )
    (net (code "94") (name "unconnected-(JTAG1-NC-Pad17)") (class "Default")
      (node (ref "JTAG1") (pin "17") (pinfunction "NC_17") (pintype "passive"))
    )
    (net (code "95") (name "unconnected-(JTAG1-NC-Pad19)") (class "Default")
      (node (ref "JTAG1") (pin "19") (pinfunction "NC_19") (pintype "passive"))
    )
  )
)
